# microphone.net
KiCad netlist of a schematic drawn in EAGLE
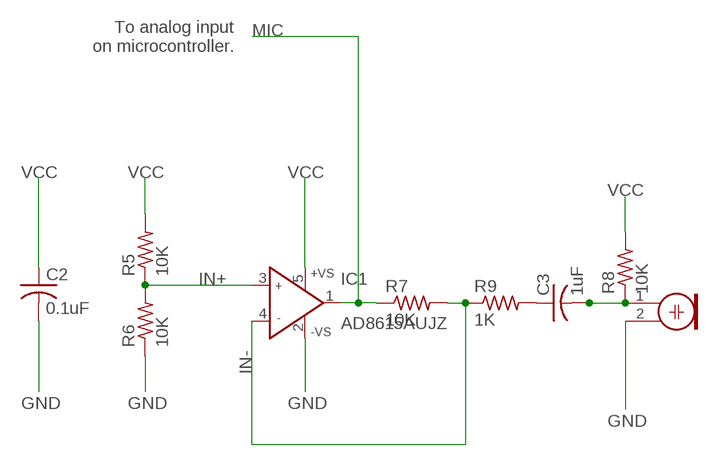
[diagram p0: schematic, sheet 1]

(export (version "E")
  (design (tool "Eeschema 10.0.6"))
  (components
    (comp (ref "C2")
      (value "0.1uF")
      (footprint "eagle-import:C1206")
      (libsource (lib "eagle-import") (part "C-USC1206"))
    )
    (comp (ref "C3")
      (value "1uF")
      (footprint "eagle-import:C1206")
      (libsource (lib "eagle-import") (part "C-USC1206"))
    )
    (comp (ref "IC1")
      (value "AD8615AUJZ")
      (footprint "eagle-import:SOT23-5")
      (fields (field (name "MF") "ALTERA CORPORATION") (field (name "MPN") "AD8614ARTZ-REEL7"))
      (libsource (lib "eagle-import") (part "AD8614RJ"))
    )
    (comp (ref "M1")
      (value "ELECTRETTH")
      (footprint "eagle-import:ELECTRET_6MM_TH")
      (libsource (lib "eagle-import") (part "ELECTRETTH"))
    )
    (comp (ref "R5")
      (value "10K")
      (footprint "eagle-import:R1206")
      (libsource (lib "eagle-import") (part "R-US_R1206"))
    )
    (comp (ref "R6")
      (value "10K")
      (footprint "eagle-import:R1206")
      (libsource (lib "eagle-import") (part "R-US_R1206"))
    )
    (comp (ref "R7")
      (value "10K")
      (footprint "eagle-import:R1206")
      (libsource (lib "eagle-import") (part "R-US_R1206"))
    )
    (comp (ref "R8")
      (value "10K")
      (footprint "eagle-import:R1206")
      (libsource (lib "eagle-import") (part "R-US_R1206"))
    )
    (comp (ref "R9")
      (value "1K")
      (footprint "eagle-import:R1206")
      (libsource (lib "eagle-import") (part "R-US_R1206"))
    )
  )
  (nets
    (net (code "1") (name "/GND") (class "Default")
      (node (ref "C2") (pin "2") (pinfunction "2_2") (pintype "passive"))
      (node (ref "IC1") (pin "2") (pinfunction "-VS_2") (pintype "input"))
      (node (ref "M1") (pin "2") (pinfunction "2_2") (pintype "passive"))
      (node (ref "R6") (pin "1") (pinfunction "1_1") (pintype "passive"))
    )
    (net (code "2") (name "/IN+") (class "Default")
      (node (ref "IC1") (pin "3") (pinfunction "IN+_3") (pintype "input"))
      (node (ref "R5") (pin "1") (pinfunction "1_1") (pintype "passive"))
      (node (ref "R6") (pin "2") (pinfunction "2_2") (pintype "passive"))
    )
    (net (code "3") (name "/IN-") (class "Default")
      (node (ref "IC1") (pin "4") (pinfunction "IN-_4") (pintype "input"))
      (node (ref "R7") (pin "2") (pinfunction "2_2") (pintype "passive"))
      (node (ref "R9") (pin "1") (pinfunction "1_1") (pintype "passive"))
    )
    (net (code "4") (name "/MIC") (class "Default")
      (node (ref "IC1") (pin "1") (pinfunction "OUT_1") (pintype "output"))
      (node (ref "R7") (pin "1") (pinfunction "1_1") (pintype "passive"))
    )
    (net (code "5") (name "/VCC") (class "Default")
      (node (ref "C2") (pin "1") (pinfunction "1_1") (pintype "passive"))
      (node (ref "IC1") (pin "5") (pinfunction "+VS_5") (pintype "input"))
      (node (ref "R5") (pin "2") (pinfunction "2_2") (pintype "passive"))
      (node (ref "R8") (pin "2") (pinfunction "2_2") (pintype "passive"))
    )
    (net (code "6") (name "Net-(C3-Pad1)") (class "Default")
      (node (ref "C3") (pin "1") (pinfunction "1_1") (pintype "passive"))
      (node (ref "R9") (pin "2") (pinfunction "2_2") (pintype "passive"))
    )
    (net (code "7") (name "Net-(C3-Pad2)") (class "Default")
      (node (ref "C3") (pin "2") (pinfunction "2_2") (pintype "passive"))
      (node (ref "M1") (pin "1") (pinfunction "1_1") (pintype "passive"))
      (node (ref "R8") (pin "1") (pinfunction "1_1") (pintype "passive"))
    )
  )
)
